# design.net
KiCad netlist of a schematic drawn in Altium Designer
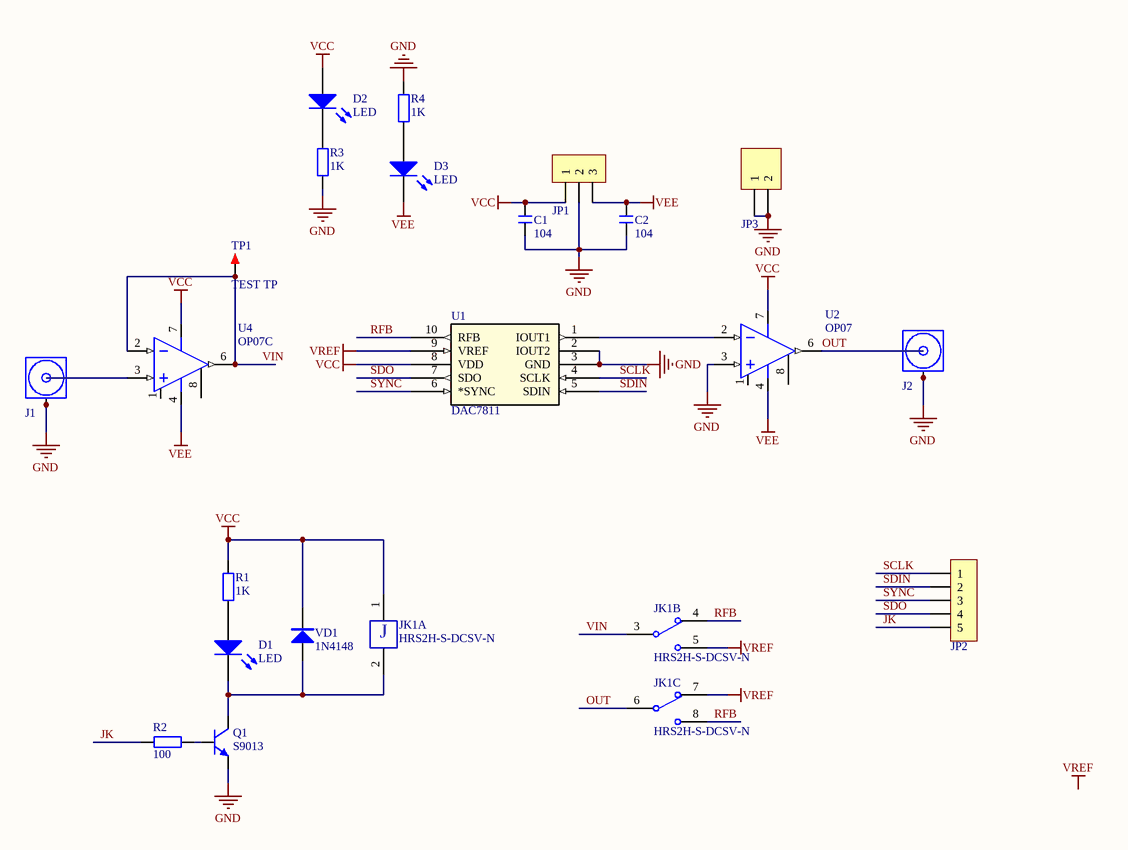
[diagram p0: 程控放大衰减电路.SchDoc]

(export (version "E")
  (design (tool "Eeschema 10.0.6"))
  (components
    (comp (ref "C1")
      (value "104")
      (footprint "C 0805")
      (description "无极性贴片电容")
      (fields (field (name "版权归属") "源创客"))
      (libsource (lib "电阻-电容-电感") (part "C"))
    )
    (comp (ref "C2")
      (value "104")
      (footprint "C 0805")
      (description "无极性贴片电容")
      (fields (field (name "版权归属") "源创客"))
      (libsource (lib "电阻-电容-电感") (part "C"))
    )
    (comp (ref "D1")
      (value "LED")
      (footprint "LED_0805")
      (description "发光二极管")
      (fields (field (name "PUBLISHER") "Altium Limited"))
      (libsource (lib "LIB") (part "LED"))
    )
    (comp (ref "D2")
      (value "LED")
      (footprint "LED_0805")
      (description "发光二极管")
      (fields (field (name "PUBLISHER") "Altium Limited"))
      (libsource (lib "LIB") (part "LED"))
    )
    (comp (ref "D3")
      (value "LED")
      (footprint "LED_0805")
      (description "发光二极管")
      (fields (field (name "PUBLISHER") "Altium Limited"))
      (libsource (lib "LIB") (part "LED"))
    )
    (comp (ref "J1") (value "COAX") (footprint "MCX5.08-5-H") (libsource (lib "LIB") (part "COAX")))
    (comp (ref "J2") (value "COAX") (footprint "MCX5.08-5-H") (libsource (lib "LIB") (part "COAX")))
    (comp (ref "JK1")
      (value "HRS2H-S-DCSV-N")
      (footprint "HRS2H")
      (description "5V双路双控继电器")
      (fields (field (name "版权归属") "源创客"))
      (libsource (lib "继电器") (part "HRS2H-S-DCSV-N_X"))
    )
    (comp (ref "JP1")
      (value "HDR-1X3")
      (footprint "HDR-1X3")
      (description "3P接插件")
      (fields (field (name "版权归属") "源创客"))
      (libsource (lib "接插件") (part "Header 3"))
    )
    (comp (ref "JP2")
      (value "HDR-1X5")
      (footprint "HDR-1X5")
      (description "5P接插件")
      (fields (field (name "版权归属") "源创客"))
      (libsource (lib "接插件") (part "Header 5"))
    )
    (comp (ref "JP3")
      (value "Header 2")
      (footprint "HDR2X1_A")
      (description "接插件")
      (fields (field (name "PUBLISHER") "Altium Limited"))
      (libsource (lib "LIB") (part "Header 2"))
    )
    (comp (ref "Q1")
      (value "S9013")
      (footprint "SOT23-3N")
      (description "低频放大-NPN型")
      (fields (field (name "版权归属") "源创客"))
      (libsource (lib "三极管") (part "9013-SMD"))
    )
    (comp (ref "R1")
      (value "1K")
      (footprint "R 0805")
      (description "贴片电阻")
      (fields (field (name "版权归属") "源创客"))
      (libsource (lib "电阻-电容-电感") (part "R"))
    )
    (comp (ref "R2")
      (value "100")
      (footprint "R 0805")
      (description "贴片电阻")
      (fields (field (name "版权归属") "源创客"))
      (libsource (lib "电阻-电容-电感") (part "R"))
    )
    (comp (ref "R3")
      (value "1K")
      (footprint "R 0805")
      (description "贴片电阻")
      (fields (field (name "版权归属") "源创客"))
      (libsource (lib "电阻-电容-电感") (part "R"))
    )
    (comp (ref "R4")
      (value "1K")
      (footprint "R 0805")
      (description "贴片电阻")
      (fields (field (name "版权归属") "源创客"))
      (libsource (lib "电阻-电容-电感") (part "R"))
    )
    (comp (ref "TP1")
      (value "TEST TP")
      (footprint "TEST TP1.4_B")
      (description "测试环")
      (fields (field (name "版权归属") "源创客"))
      (libsource (lib "未分类器件") (part "TEST TP"))
    )
    (comp (ref "U1")
      (value "DAC7811")
      (footprint "VSSOP 10 (DGK)")
      (description "12-Bit, Serial Input, Multiplying Digital-to-Analog Converter")
      (fields
        (field (name "MANUFACTURER") "Texas Instruments")
        (field (name "MANUFACTURER_PART_NUMBER") "dac7811_dgs_10")
      )
      (libsource (lib "LIB") (part "DAC7811"))
    )
    (comp (ref "U2")
      (value "OP07")
      (footprint "SO8_L")
      (description "Precision Operational Amplifiers")
      (libsource (lib "LIB") (part "OP07"))
    )
    (comp (ref "U4")
      (value "OP07C")
      (footprint "SO8_L")
      (description "Precision Operational Amplifiers")
      (libsource (lib "LIB") (part "OP07"))
    )
    (comp (ref "VD1")
      (value "1N4148")
      (footprint "SOD-323")
      (description "高速开关二极管")
      (fields (field (name "版权归属") "源创客"))
      (libsource (lib "二极管-整流桥") (part "1N4148"))
    )
  )
  (nets
    (net (code "1") (name "/JK") (class "Default")
      (node (ref "JP2") (pin "5") (pinfunction "5_5") (pintype "passive"))
      (node (ref "R2") (pin "1") (pinfunction "1_1") (pintype "passive"))
    )
    (net (code "2") (name "/OUT") (class "Default")
      (node (ref "J2") (pin "1") (pinfunction "Signal_1") (pintype "passive"))
      (node (ref "JK1") (pin "6") (pinfunction "6_6") (pintype "passive"))
      (node (ref "U2") (pin "6") (pinfunction "OUT_6") (pintype "output"))
    )
    (net (code "3") (name "/RFB") (class "Default")
      (node (ref "JK1") (pin "4") (pinfunction "4_4") (pintype "passive"))
      (node (ref "JK1") (pin "8") (pinfunction "8_8") (pintype "passive"))
      (node (ref "U1") (pin "10") (pinfunction "RFB_10") (pintype "output"))
    )
    (net (code "4") (name "/SCLK") (class "Default")
      (node (ref "JP2") (pin "1") (pinfunction "1_1") (pintype "passive"))
      (node (ref "U1") (pin "4") (pinfunction "SCLK_4") (pintype "input"))
    )
    (net (code "5") (name "/SDIN") (class "Default")
      (node (ref "JP2") (pin "2") (pinfunction "2_2") (pintype "passive"))
      (node (ref "U1") (pin "5") (pinfunction "SDIN_5") (pintype "input"))
    )
    (net (code "6") (name "/SDO") (class "Default")
      (node (ref "JP2") (pin "4") (pinfunction "4_4") (pintype "passive"))
      (node (ref "U1") (pin "7") (pinfunction "SDO_7") (pintype "output"))
    )
    (net (code "7") (name "/SYNC") (class "Default")
      (node (ref "JP2") (pin "3") (pinfunction "3_3") (pintype "passive"))
      (node (ref "U1") (pin "6") (pinfunction "*SYNC_6") (pintype "input"))
    )
    (net (code "8") (name "/VIN") (class "Default")
      (node (ref "JK1") (pin "3") (pinfunction "3_3") (pintype "passive"))
      (node (ref "TP1") (pin "1") (pinfunction "1_1") (pintype "passive"))
      (node (ref "U4") (pin "2") (pinfunction "IN-_2") (pintype "input"))
      (node (ref "U4") (pin "6") (pinfunction "OUT_6") (pintype "output"))
    )
    (net (code "9") (name "GND") (class "Default")
      (node (ref "C1") (pin "1") (pinfunction "1_1") (pintype "passive"))
      (node (ref "C2") (pin "1") (pinfunction "1_1") (pintype "passive"))
      (node (ref "J1") (pin "2") (pinfunction "GND_2") (pintype "passive"))
      (node (ref "J1") (pin "3") (pinfunction "GND_3") (pintype "passive"))
      (node (ref "J1") (pin "4") (pinfunction "GND_4") (pintype "passive"))
      (node (ref "J1") (pin "5") (pinfunction "GND_5") (pintype "passive"))
      (node (ref "J2") (pin "2") (pinfunction "GND_2") (pintype "passive"))
      (node (ref "J2") (pin "3") (pinfunction "GND_3") (pintype "passive"))
      (node (ref "J2") (pin "4") (pinfunction "GND_4") (pintype "passive"))
      (node (ref "J2") (pin "5") (pinfunction "GND_5") (pintype "passive"))
      (node (ref "JP1") (pin "2") (pinfunction "2_2") (pintype "passive"))
      (node (ref "JP3") (pin "1") (pinfunction "1_1") (pintype "passive"))
      (node (ref "JP3") (pin "2") (pinfunction "2_2") (pintype "passive"))
      (node (ref "Q1") (pin "2") (pinfunction "E_2") (pintype "passive"))
      (node (ref "R3") (pin "1") (pinfunction "1_1") (pintype "passive"))
      (node (ref "R4") (pin "2") (pinfunction "2_2") (pintype "passive"))
      (node (ref "U1") (pin "2") (pinfunction "IOUT2_2") (pintype "passive"))
      (node (ref "U1") (pin "3") (pinfunction "GND_3") (pintype "power_in"))
      (node (ref "U2") (pin "3") (pinfunction "IN+_3") (pintype "input"))
    )
    (net (code "10") (name "Net-(D1-A)") (class "Default")
      (node (ref "D1") (pin "1") (pinfunction "A_1") (pintype "passive"))
      (node (ref "R1") (pin "1") (pinfunction "1_1") (pintype "passive"))
    )
    (net (code "11") (name "Net-(D1-K)") (class "Default")
      (node (ref "D1") (pin "2") (pinfunction "K_2") (pintype "passive"))
      (node (ref "JK1") (pin "2") (pinfunction "2_2") (pintype "passive"))
      (node (ref "Q1") (pin "3") (pinfunction "C_3") (pintype "passive"))
      (node (ref "VD1") (pin "1") (pinfunction "A_1") (pintype "passive"))
    )
    (net (code "12") (name "Net-(D2-K)") (class "Default")
      (node (ref "D2") (pin "2") (pinfunction "K_2") (pintype "passive"))
      (node (ref "R3") (pin "2") (pinfunction "2_2") (pintype "passive"))
    )
    (net (code "13") (name "Net-(D3-A)") (class "Default")
      (node (ref "D3") (pin "1") (pinfunction "A_1") (pintype "passive"))
      (node (ref "R4") (pin "1") (pinfunction "1_1") (pintype "passive"))
    )
    (net (code "14") (name "Net-(J1-Signal)") (class "Default")
      (node (ref "J1") (pin "1") (pinfunction "Signal_1") (pintype "passive"))
      (node (ref "U4") (pin "3") (pinfunction "IN+_3") (pintype "input"))
    )
    (net (code "15") (name "Net-(Q1-B)") (class "Default")
      (node (ref "Q1") (pin "1") (pinfunction "B_1") (pintype "passive"))
      (node (ref "R2") (pin "2") (pinfunction "2_2") (pintype "passive"))
    )
    (net (code "16") (name "Net-(U1-IOUT1)") (class "Default")
      (node (ref "U1") (pin "1") (pinfunction "IOUT1_1") (pintype "output"))
      (node (ref "U2") (pin "2") (pinfunction "IN-_2") (pintype "input"))
    )
    (net (code "17") (name "VCC") (class "Default")
      (node (ref "C1") (pin "2") (pinfunction "2_2") (pintype "passive"))
      (node (ref "D2") (pin "1") (pinfunction "A_1") (pintype "passive"))
      (node (ref "JK1") (pin "1") (pinfunction "1_1") (pintype "passive"))
      (node (ref "JP1") (pin "1") (pinfunction "1_1") (pintype "passive"))
      (node (ref "R1") (pin "2") (pinfunction "2_2") (pintype "passive"))
      (node (ref "U1") (pin "8") (pinfunction "VDD_8") (pintype "power_in"))
      (node (ref "U2") (pin "7") (pinfunction "V+_7") (pintype "power_in"))
      (node (ref "U4") (pin "7") (pinfunction "V+_7") (pintype "power_in"))
      (node (ref "VD1") (pin "2") (pinfunction "K_2") (pintype "passive"))
    )
    (net (code "18") (name "VEE") (class "Default")
      (node (ref "C2") (pin "2") (pinfunction "2_2") (pintype "passive"))
      (node (ref "D3") (pin "2") (pinfunction "K_2") (pintype "passive"))
      (node (ref "JP1") (pin "3") (pinfunction "3_3") (pintype "passive"))
      (node (ref "U2") (pin "4") (pinfunction "V-_4") (pintype "power_in"))
      (node (ref "U4") (pin "4") (pinfunction "V-_4") (pintype "power_in"))
    )
    (net (code "19") (name "VREF") (class "Default")
      (node (ref "JK1") (pin "5") (pinfunction "5_5") (pintype "passive"))
      (node (ref "JK1") (pin "7") (pinfunction "7_7") (pintype "passive"))
      (node (ref "U1") (pin "9") (pinfunction "VREF_9") (pintype "input"))
    )
    (net (code "20") (name "unconnected-(U2-OFFSET_N1-Pad1)") (class "Default")
      (node (ref "U2") (pin "1") (pinfunction "OFFSET_N1_1") (pintype "passive"))
    )
    (net (code "21") (name "unconnected-(U2-OFFSET_N2-Pad8)") (class "Default")
      (node (ref "U2") (pin "8") (pinfunction "OFFSET_N2_8") (pintype "passive"))
    )
    (net (code "22") (name "unconnected-(U4-OFFSET_N1-Pad1)") (class "Default")
      (node (ref "U4") (pin "1") (pinfunction "OFFSET_N1_1") (pintype "passive"))
    )
    (net (code "23") (name "unconnected-(U4-OFFSET_N2-Pad8)") (class "Default")
      (node (ref "U4") (pin "8") (pinfunction "OFFSET_N2_8") (pintype "passive"))
    )
  )
)
